# psu.net
KiCad netlist of a schematic drawn in EAGLE
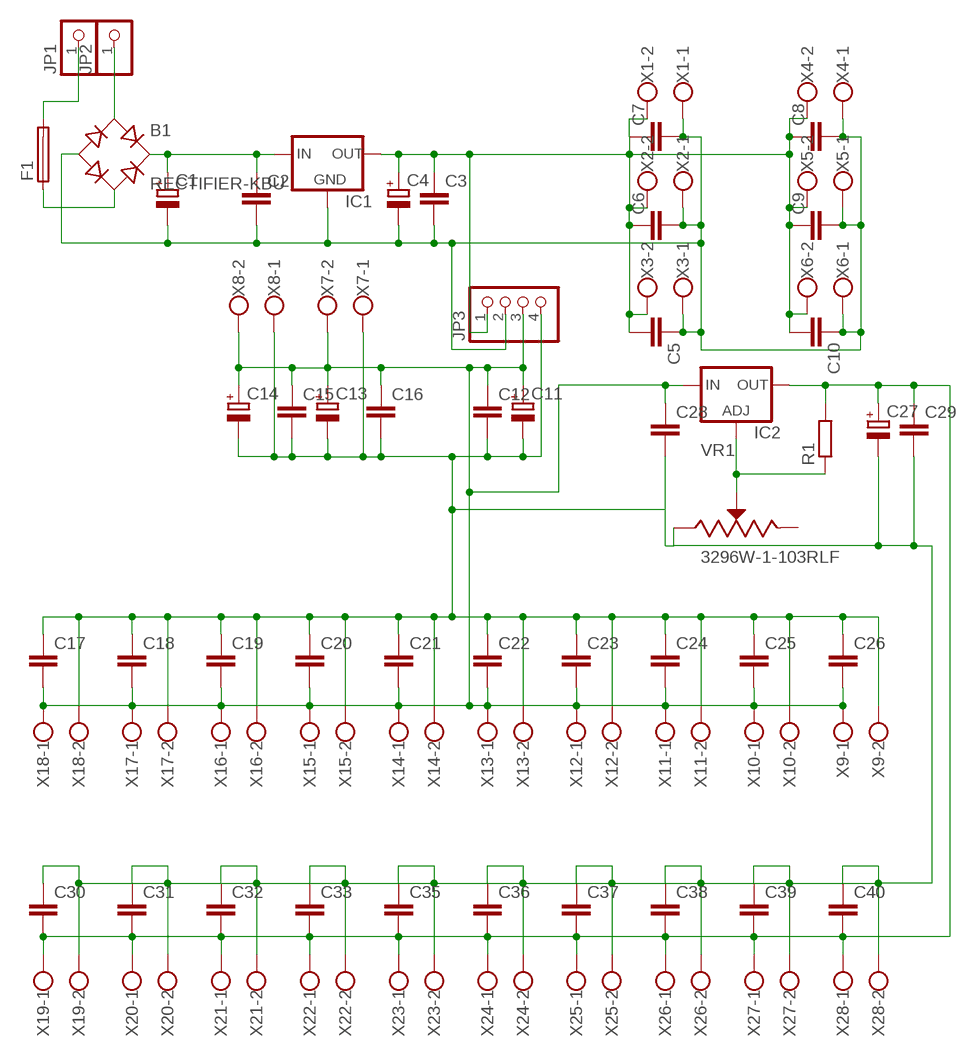
[diagram p0: schematic, sheet 1]

(export (version "E")
  (design (tool "Eeschema 10.0.6"))
  (components
    (comp (ref "B1")
      (value "RECTIFIER-KBU")
      (footprint "eagle-import:KBU")
      (libsource (lib "eagle-import") (part "RECTIFIER-KBU"))
    )
    (comp (ref "C1")
      (value "CPOL-EUE7.5-18")
      (footprint "eagle-import:E7,5-18")
      (libsource (lib "eagle-import") (part "CPOL-EUE7.5-18"))
    )
    (comp (ref "C2")
      (value "C-EU025-025X050")
      (footprint "eagle-import:C025-025X050")
      (libsource (lib "eagle-import") (part "C-EU025-025X050"))
    )
    (comp (ref "C3")
      (value "C-EU025-025X050")
      (footprint "eagle-import:C025-025X050")
      (libsource (lib "eagle-import") (part "C-EU025-025X050"))
    )
    (comp (ref "C4")
      (value "CPOL-EUE5-10.5")
      (footprint "eagle-import:E5-10,5")
      (libsource (lib "eagle-import") (part "CPOL-EUE5-10.5"))
    )
    (comp (ref "C5")
      (value "C-EU025-025X050")
      (footprint "eagle-import:C025-025X050")
      (libsource (lib "eagle-import") (part "C-EU025-025X050"))
    )
    (comp (ref "C6")
      (value "C-EU025-025X050")
      (footprint "eagle-import:C025-025X050")
      (libsource (lib "eagle-import") (part "C-EU025-025X050"))
    )
    (comp (ref "C7")
      (value "C-EU025-025X050")
      (footprint "eagle-import:C025-025X050")
      (libsource (lib "eagle-import") (part "C-EU025-025X050"))
    )
    (comp (ref "C8")
      (value "C-EU025-025X050")
      (footprint "eagle-import:C025-025X050")
      (libsource (lib "eagle-import") (part "C-EU025-025X050"))
    )
    (comp (ref "C9")
      (value "C-EU025-025X050")
      (footprint "eagle-import:C025-025X050")
      (libsource (lib "eagle-import") (part "C-EU025-025X050"))
    )
    (comp (ref "C10")
      (value "C-EU025-025X050")
      (footprint "eagle-import:C025-025X050")
      (libsource (lib "eagle-import") (part "C-EU025-025X050"))
    )
    (comp (ref "C11")
      (value "CPOL-EUE5-10.5")
      (footprint "eagle-import:E5-10,5")
      (libsource (lib "eagle-import") (part "CPOL-EUE5-10.5"))
    )
    (comp (ref "C12")
      (value "C-EU025-025X050")
      (footprint "eagle-import:C025-025X050")
      (libsource (lib "eagle-import") (part "C-EU025-025X050"))
    )
    (comp (ref "C13")
      (value "CPOL-EUE2.5-6")
      (footprint "eagle-import:E2,5-6")
      (libsource (lib "eagle-import") (part "CPOL-EUE2.5-6"))
    )
    (comp (ref "C14")
      (value "CPOL-EUE2.5-6")
      (footprint "eagle-import:E2,5-6")
      (libsource (lib "eagle-import") (part "CPOL-EUE2.5-6"))
    )
    (comp (ref "C15")
      (value "C-EU025-025X050")
      (footprint "eagle-import:C025-025X050")
      (libsource (lib "eagle-import") (part "C-EU025-025X050"))
    )
    (comp (ref "C16")
      (value "C-EU025-025X050")
      (footprint "eagle-import:C025-025X050")
      (libsource (lib "eagle-import") (part "C-EU025-025X050"))
    )
    (comp (ref "C17")
      (value "C-EU025-025X050")
      (footprint "eagle-import:C025-025X050")
      (libsource (lib "eagle-import") (part "C-EU025-025X050"))
    )
    (comp (ref "C18")
      (value "C-EU025-025X050")
      (footprint "eagle-import:C025-025X050")
      (libsource (lib "eagle-import") (part "C-EU025-025X050"))
    )
    (comp (ref "C19")
      (value "C-EU025-025X050")
      (footprint "eagle-import:C025-025X050")
      (libsource (lib "eagle-import") (part "C-EU025-025X050"))
    )
    (comp (ref "C20")
      (value "C-EU025-025X050")
      (footprint "eagle-import:C025-025X050")
      (libsource (lib "eagle-import") (part "C-EU025-025X050"))
    )
    (comp (ref "C21")
      (value "C-EU025-025X050")
      (footprint "eagle-import:C025-025X050")
      (libsource (lib "eagle-import") (part "C-EU025-025X050"))
    )
    (comp (ref "C22")
      (value "C-EU025-025X050")
      (footprint "eagle-import:C025-025X050")
      (libsource (lib "eagle-import") (part "C-EU025-025X050"))
    )
    (comp (ref "C23")
      (value "C-EU025-025X050")
      (footprint "eagle-import:C025-025X050")
      (libsource (lib "eagle-import") (part "C-EU025-025X050"))
    )
    (comp (ref "C24")
      (value "C-EU025-025X050")
      (footprint "eagle-import:C025-025X050")
      (libsource (lib "eagle-import") (part "C-EU025-025X050"))
    )
    (comp (ref "C25")
      (value "C-EU025-025X050")
      (footprint "eagle-import:C025-025X050")
      (libsource (lib "eagle-import") (part "C-EU025-025X050"))
    )
    (comp (ref "C26")
      (value "C-EU025-025X050")
      (footprint "eagle-import:C025-025X050")
      (libsource (lib "eagle-import") (part "C-EU025-025X050"))
    )
    (comp (ref "C27")
      (value "CPOL-EUE2.5-6")
      (footprint "eagle-import:E2,5-6")
      (libsource (lib "eagle-import") (part "CPOL-EUE2.5-6"))
    )
    (comp (ref "C28")
      (value "C-EU025-025X050")
      (footprint "eagle-import:C025-025X050")
      (libsource (lib "eagle-import") (part "C-EU025-025X050"))
    )
    (comp (ref "C29")
      (value "C-EU025-025X050")
      (footprint "eagle-import:C025-025X050")
      (libsource (lib "eagle-import") (part "C-EU025-025X050"))
    )
    (comp (ref "C30")
      (value "C-EU025-025X050")
      (footprint "eagle-import:C025-025X050")
      (libsource (lib "eagle-import") (part "C-EU025-025X050"))
    )
    (comp (ref "C31")
      (value "C-EU025-025X050")
      (footprint "eagle-import:C025-025X050")
      (libsource (lib "eagle-import") (part "C-EU025-025X050"))
    )
    (comp (ref "C32")
      (value "C-EU025-025X050")
      (footprint "eagle-import:C025-025X050")
      (libsource (lib "eagle-import") (part "C-EU025-025X050"))
    )
    (comp (ref "C33")
      (value "C-EU025-025X050")
      (footprint "eagle-import:C025-025X050")
      (libsource (lib "eagle-import") (part "C-EU025-025X050"))
    )
    (comp (ref "C35")
      (value "C-EU025-025X050")
      (footprint "eagle-import:C025-025X050")
      (libsource (lib "eagle-import") (part "C-EU025-025X050"))
    )
    (comp (ref "C36")
      (value "C-EU025-025X050")
      (footprint "eagle-import:C025-025X050")
      (libsource (lib "eagle-import") (part "C-EU025-025X050"))
    )
    (comp (ref "C37")
      (value "C-EU025-025X050")
      (footprint "eagle-import:C025-025X050")
      (libsource (lib "eagle-import") (part "C-EU025-025X050"))
    )
    (comp (ref "C38")
      (value "C-EU025-025X050")
      (footprint "eagle-import:C025-025X050")
      (libsource (lib "eagle-import") (part "C-EU025-025X050"))
    )
    (comp (ref "C39")
      (value "C-EU025-025X050")
      (footprint "eagle-import:C025-025X050")
      (libsource (lib "eagle-import") (part "C-EU025-025X050"))
    )
    (comp (ref "C40")
      (value "C-EU025-025X050")
      (footprint "eagle-import:C025-025X050")
      (libsource (lib "eagle-import") (part "C-EU025-025X050"))
    )
    (comp (ref "F1")
      (value "SH22,5")
      (footprint "eagle-import:SH22,5")
      (fields (field (name "MF") "SCHURTER") (field (name "MPN") "0031.8201"))
      (libsource (lib "eagle-import") (part "SH22,5"))
    )
    (comp (ref "IC1")
      (value "78XXS")
      (footprint "eagle-import:78XXS")
      (libsource (lib "eagle-import") (part "78XXS"))
    )
    (comp (ref "IC2")
      (value "LM317TS")
      (footprint "eagle-import:317TS")
      (libsource (lib "eagle-import") (part "LM317TS"))
    )
    (comp (ref "JP1")
      (value "PINHD-1X1")
      (footprint "eagle-import:1X01")
      (libsource (lib "eagle-import") (part "PINHD-1X1"))
    )
    (comp (ref "JP2")
      (value "PINHD-1X1")
      (footprint "eagle-import:1X01")
      (libsource (lib "eagle-import") (part "PINHD-1X1"))
    )
    (comp (ref "JP3")
      (value "PINHD-1X4")
      (footprint "eagle-import:1X04")
      (libsource (lib "eagle-import") (part "PINHD-1X4"))
    )
    (comp (ref "R1")
      (value "R-EU_0204/7")
      (footprint "eagle-import:0204_7")
      (libsource (lib "eagle-import") (part "R-EU_0204/7"))
    )
    (comp (ref "VR1")
      (value "3296W-1-103RLF")
      (footprint "eagle-import:TRIM_3296W-1-103RLF")
      (fields (field (name "MF") "Bourns"))
      (libsource (lib "eagle-import") (part "3296W-1-103RLF"))
    )
    (comp (ref "X1")
      (value "W237-102")
      (footprint "eagle-import:W237-102")
      (fields (field (name "MPN") "237-102"))
      (libsource (lib "eagle-import") (part "W237-102"))
    )
    (comp (ref "X2")
      (value "W237-102")
      (footprint "eagle-import:W237-102")
      (fields (field (name "MPN") "237-102"))
      (libsource (lib "eagle-import") (part "W237-102"))
    )
    (comp (ref "X3")
      (value "W237-102")
      (footprint "eagle-import:W237-102")
      (fields (field (name "MPN") "237-102"))
      (libsource (lib "eagle-import") (part "W237-102"))
    )
    (comp (ref "X4")
      (value "W237-102")
      (footprint "eagle-import:W237-102")
      (fields (field (name "MPN") "237-102"))
      (libsource (lib "eagle-import") (part "W237-102"))
    )
    (comp (ref "X5")
      (value "W237-102")
      (footprint "eagle-import:W237-102")
      (fields (field (name "MPN") "237-102"))
      (libsource (lib "eagle-import") (part "W237-102"))
    )
    (comp (ref "X6")
      (value "W237-102")
      (footprint "eagle-import:W237-102")
      (fields (field (name "MPN") "237-102"))
      (libsource (lib "eagle-import") (part "W237-102"))
    )
    (comp (ref "X7")
      (value "W237-102")
      (footprint "eagle-import:W237-102")
      (fields (field (name "MPN") "237-102"))
      (libsource (lib "eagle-import") (part "W237-102"))
    )
    (comp (ref "X8")
      (value "W237-102")
      (footprint "eagle-import:W237-102")
      (fields (field (name "MPN") "237-102"))
      (libsource (lib "eagle-import") (part "W237-102"))
    )
    (comp (ref "X9")
      (value "W237-102")
      (footprint "eagle-import:W237-102")
      (fields (field (name "MPN") "237-102"))
      (libsource (lib "eagle-import") (part "W237-102"))
    )
    (comp (ref "X10")
      (value "W237-102")
      (footprint "eagle-import:W237-102")
      (fields (field (name "MPN") "237-102"))
      (libsource (lib "eagle-import") (part "W237-102"))
    )
    (comp (ref "X11")
      (value "W237-102")
      (footprint "eagle-import:W237-102")
      (fields (field (name "MPN") "237-102"))
      (libsource (lib "eagle-import") (part "W237-102"))
    )
    (comp (ref "X12")
      (value "W237-102")
      (footprint "eagle-import:W237-102")
      (fields (field (name "MPN") "237-102"))
      (libsource (lib "eagle-import") (part "W237-102"))
    )
    (comp (ref "X13")
      (value "W237-102")
      (footprint "eagle-import:W237-102")
      (fields (field (name "MPN") "237-102"))
      (libsource (lib "eagle-import") (part "W237-102"))
    )
    (comp (ref "X14")
      (value "W237-102")
      (footprint "eagle-import:W237-102")
      (fields (field (name "MPN") "237-102"))
      (libsource (lib "eagle-import") (part "W237-102"))
    )
    (comp (ref "X15")
      (value "W237-102")
      (footprint "eagle-import:W237-102")
      (fields (field (name "MPN") "237-102"))
      (libsource (lib "eagle-import") (part "W237-102"))
    )
    (comp (ref "X16")
      (value "W237-102")
      (footprint "eagle-import:W237-102")
      (fields (field (name "MPN") "237-102"))
      (libsource (lib "eagle-import") (part "W237-102"))
    )
    (comp (ref "X17")
      (value "W237-102")
      (footprint "eagle-import:W237-102")
      (fields (field (name "MPN") "237-102"))
      (libsource (lib "eagle-import") (part "W237-102"))
    )
    (comp (ref "X18")
      (value "W237-102")
      (footprint "eagle-import:W237-102")
      (fields (field (name "MPN") "237-102"))
      (libsource (lib "eagle-import") (part "W237-102"))
    )
    (comp (ref "X19")
      (value "W237-102")
      (footprint "eagle-import:W237-102")
      (fields (field (name "MPN") "237-102"))
      (libsource (lib "eagle-import") (part "W237-102"))
    )
    (comp (ref "X20")
      (value "W237-102")
      (footprint "eagle-import:W237-102")
      (fields (field (name "MPN") "237-102"))
      (libsource (lib "eagle-import") (part "W237-102"))
    )
    (comp (ref "X21")
      (value "W237-102")
      (footprint "eagle-import:W237-102")
      (fields (field (name "MPN") "237-102"))
      (libsource (lib "eagle-import") (part "W237-102"))
    )
    (comp (ref "X22")
      (value "W237-102")
      (footprint "eagle-import:W237-102")
      (fields (field (name "MPN") "237-102"))
      (libsource (lib "eagle-import") (part "W237-102"))
    )
    (comp (ref "X23")
      (value "W237-102")
      (footprint "eagle-import:W237-102")
      (fields (field (name "MPN") "237-102"))
      (libsource (lib "eagle-import") (part "W237-102"))
    )
    (comp (ref "X24")
      (value "W237-102")
      (footprint "eagle-import:W237-102")
      (fields (field (name "MPN") "237-102"))
      (libsource (lib "eagle-import") (part "W237-102"))
    )
    (comp (ref "X25")
      (value "W237-102")
      (footprint "eagle-import:W237-102")
      (fields (field (name "MPN") "237-102"))
      (libsource (lib "eagle-import") (part "W237-102"))
    )
    (comp (ref "X26")
      (value "W237-102")
      (footprint "eagle-import:W237-102")
      (fields (field (name "MPN") "237-102"))
      (libsource (lib "eagle-import") (part "W237-102"))
    )
    (comp (ref "X27")
      (value "W237-102")
      (footprint "eagle-import:W237-102")
      (fields (field (name "MPN") "237-102"))
      (libsource (lib "eagle-import") (part "W237-102"))
    )
    (comp (ref "X28")
      (value "W237-102")
      (footprint "eagle-import:W237-102")
      (fields (field (name "MPN") "237-102"))
      (libsource (lib "eagle-import") (part "W237-102"))
    )
  )
  (nets
    (net (code "1") (name "Net-(B1-Pad+)") (class "Default")
      (node (ref "B1") (pin "+") (pinfunction "+_+") (pintype "passive"))
      (node (ref "C1") (pin "+") (pinfunction "+_+") (pintype "passive"))
      (node (ref "C2") (pin "1") (pinfunction "1_1") (pintype "passive"))
      (node (ref "IC1") (pin "IN") (pinfunction "IN_IN") (pintype "input"))
    )
    (net (code "2") (name "Net-(B1-PadAC1)") (class "Default")
      (node (ref "B1") (pin "AC1") (pinfunction "AC1_AC1") (pintype "passive"))
      (node (ref "JP2") (pin "1") (pinfunction "1_1") (pintype "passive"))
    )
    (net (code "3") (name "Net-(B1-PadAC2)") (class "Default")
      (node (ref "B1") (pin "AC2") (pinfunction "AC2_AC2") (pintype "passive"))
      (node (ref "F1") (pin "1") (pinfunction "1_1") (pintype "passive"))
    )
    (net (code "4") (name "Net-(F1-Pad2)") (class "Default")
      (node (ref "F1") (pin "2") (pinfunction "2_2") (pintype "passive"))
      (node (ref "JP1") (pin "1") (pinfunction "1_1") (pintype "passive"))
    )
    (net (code "5") (name "Net-(IC2-ADJ)") (class "Default")
      (node (ref "IC2") (pin "1") (pinfunction "ADJ_1") (pintype "input"))
      (node (ref "R1") (pin "1") (pinfunction "1_1") (pintype "passive"))
      (node (ref "VR1") (pin "2") (pinfunction "WIPER_2") (pintype "passive"))
    )
    (net (code "6") (name "Net-(IC2-IN)") (class "Default")
      (node (ref "C11") (pin "+") (pinfunction "+_+") (pintype "passive"))
      (node (ref "C12") (pin "1") (pinfunction "1_1") (pintype "passive"))
      (node (ref "C13") (pin "+") (pinfunction "+_+") (pintype "passive"))
      (node (ref "C14") (pin "+") (pinfunction "+_+") (pintype "passive"))
      (node (ref "C15") (pin "1") (pinfunction "1_1") (pintype "passive"))
      (node (ref "C16") (pin "1") (pinfunction "1_1") (pintype "passive"))
      (node (ref "C17") (pin "2") (pinfunction "2_2") (pintype "passive"))
      (node (ref "C18") (pin "2") (pinfunction "2_2") (pintype "passive"))
      (node (ref "C19") (pin "2") (pinfunction "2_2") (pintype "passive"))
      (node (ref "C20") (pin "2") (pinfunction "2_2") (pintype "passive"))
      (node (ref "C21") (pin "2") (pinfunction "2_2") (pintype "passive"))
      (node (ref "C22") (pin "2") (pinfunction "2_2") (pintype "passive"))
      (node (ref "C23") (pin "2") (pinfunction "2_2") (pintype "passive"))
      (node (ref "C24") (pin "2") (pinfunction "2_2") (pintype "passive"))
      (node (ref "C25") (pin "2") (pinfunction "2_2") (pintype "passive"))
      (node (ref "C26") (pin "2") (pinfunction "2_2") (pintype "passive"))
      (node (ref "C28") (pin "1") (pinfunction "1_1") (pintype "passive"))
      (node (ref "IC2") (pin "3") (pinfunction "IN_3") (pintype "input"))
      (node (ref "JP3") (pin "3") (pinfunction "3_3") (pintype "passive"))
      (node (ref "X10") (pin "1") (pinfunction "KL_1") (pintype "passive"))
      (node (ref "X11") (pin "1") (pinfunction "KL_1") (pintype "passive"))
      (node (ref "X12") (pin "1") (pinfunction "KL_1") (pintype "passive"))
      (node (ref "X13") (pin "1") (pinfunction "KL_1") (pintype "passive"))
      (node (ref "X14") (pin "1") (pinfunction "KL_1") (pintype "passive"))
      (node (ref "X15") (pin "1") (pinfunction "KL_1") (pintype "passive"))
      (node (ref "X16") (pin "1") (pinfunction "KL_1") (pintype "passive"))
      (node (ref "X17") (pin "1") (pinfunction "KL_1") (pintype "passive"))
      (node (ref "X18") (pin "1") (pinfunction "KL_1") (pintype "passive"))
      (node (ref "X7") (pin "2") (pinfunction "KL_2") (pintype "passive"))
      (node (ref "X8") (pin "2") (pinfunction "KL_2") (pintype "passive"))
      (node (ref "X9") (pin "1") (pinfunction "KL_1") (pintype "passive"))
    )
    (net (code "7") (name "Net-(IC2-OUT)") (class "Default")
      (node (ref "C27") (pin "+") (pinfunction "+_+") (pintype "passive"))
      (node (ref "C29") (pin "1") (pinfunction "1_1") (pintype "passive"))
      (node (ref "C30") (pin "2") (pinfunction "2_2") (pintype "passive"))
      (node (ref "C31") (pin "2") (pinfunction "2_2") (pintype "passive"))
      (node (ref "C32") (pin "2") (pinfunction "2_2") (pintype "passive"))
      (node (ref "C33") (pin "2") (pinfunction "2_2") (pintype "passive"))
      (node (ref "C35") (pin "2") (pinfunction "2_2") (pintype "passive"))
      (node (ref "C36") (pin "2") (pinfunction "2_2") (pintype "passive"))
      (node (ref "C37") (pin "2") (pinfunction "2_2") (pintype "passive"))
      (node (ref "C38") (pin "2") (pinfunction "2_2") (pintype "passive"))
      (node (ref "C39") (pin "2") (pinfunction "2_2") (pintype "passive"))
      (node (ref "C40") (pin "2") (pinfunction "2_2") (pintype "passive"))
      (node (ref "IC2") (pin "2") (pinfunction "OUT_2") (pintype "passive"))
      (node (ref "R1") (pin "2") (pinfunction "2_2") (pintype "passive"))
      (node (ref "X19") (pin "1") (pinfunction "KL_1") (pintype "passive"))
      (node (ref "X20") (pin "1") (pinfunction "KL_1") (pintype "passive"))
      (node (ref "X21") (pin "1") (pinfunction "KL_1") (pintype "passive"))
      (node (ref "X22") (pin "1") (pinfunction "KL_1") (pintype "passive"))
      (node (ref "X23") (pin "1") (pinfunction "KL_1") (pintype "passive"))
      (node (ref "X24") (pin "1") (pinfunction "KL_1") (pintype "passive"))
      (node (ref "X25") (pin "1") (pinfunction "KL_1") (pintype "passive"))
      (node (ref "X26") (pin "1") (pinfunction "KL_1") (pintype "passive"))
      (node (ref "X27") (pin "1") (pinfunction "KL_1") (pintype "passive"))
      (node (ref "X28") (pin "1") (pinfunction "KL_1") (pintype "passive"))
    )
    (net (code "8") (name "Net-(VR1-CCW)") (class "Default")
      (node (ref "C11") (pin "-") (pinfunction "-_-") (pintype "passive"))
      (node (ref "C12") (pin "2") (pinfunction "2_2") (pintype "passive"))
      (node (ref "C13") (pin "-") (pinfunction "-_-") (pintype "passive"))
      (node (ref "C14") (pin "-") (pinfunction "-_-") (pintype "passive"))
      (node (ref "C15") (pin "2") (pinfunction "2_2") (pintype "passive"))
      (node (ref "C16") (pin "2") (pinfunction "2_2") (pintype "passive"))
      (node (ref "C17") (pin "1") (pinfunction "1_1") (pintype "passive"))
      (node (ref "C18") (pin "1") (pinfunction "1_1") (pintype "passive"))
      (node (ref "C19") (pin "1") (pinfunction "1_1") (pintype "passive"))
      (node (ref "C20") (pin "1") (pinfunction "1_1") (pintype "passive"))
      (node (ref "C21") (pin "1") (pinfunction "1_1") (pintype "passive"))
      (node (ref "C22") (pin "1") (pinfunction "1_1") (pintype "passive"))
      (node (ref "C23") (pin "1") (pinfunction "1_1") (pintype "passive"))
      (node (ref "C24") (pin "1") (pinfunction "1_1") (pintype "passive"))
      (node (ref "C25") (pin "1") (pinfunction "1_1") (pintype "passive"))
      (node (ref "C26") (pin "1") (pinfunction "1_1") (pintype "passive"))
      (node (ref "C27") (pin "-") (pinfunction "-_-") (pintype "passive"))
      (node (ref "C28") (pin "2") (pinfunction "2_2") (pintype "passive"))
      (node (ref "C29") (pin "2") (pinfunction "2_2") (pintype "passive"))
      (node (ref "C30") (pin "1") (pinfunction "1_1") (pintype "passive"))
      (node (ref "C31") (pin "1") (pinfunction "1_1") (pintype "passive"))
      (node (ref "C32") (pin "1") (pinfunction "1_1") (pintype "passive"))
      (node (ref "C33") (pin "1") (pinfunction "1_1") (pintype "passive"))
      (node (ref "C35") (pin "1") (pinfunction "1_1") (pintype "passive"))
      (node (ref "C36") (pin "1") (pinfunction "1_1") (pintype "passive"))
      (node (ref "C37") (pin "1") (pinfunction "1_1") (pintype "passive"))
      (node (ref "C38") (pin "1") (pinfunction "1_1") (pintype "passive"))
      (node (ref "C39") (pin "1") (pinfunction "1_1") (pintype "passive"))
      (node (ref "C40") (pin "1") (pinfunction "1_1") (pintype "passive"))
      (node (ref "JP3") (pin "4") (pinfunction "4_4") (pintype "passive"))
      (node (ref "VR1") (pin "1") (pinfunction "CCW_1") (pintype "passive"))
      (node (ref "X10") (pin "2") (pinfunction "KL_2") (pintype "passive"))
      (node (ref "X11") (pin "2") (pinfunction "KL_2") (pintype "passive"))
      (node (ref "X12") (pin "2") (pinfunction "KL_2") (pintype "passive"))
      (node (ref "X13") (pin "2") (pinfunction "KL_2") (pintype "passive"))
      (node (ref "X14") (pin "2") (pinfunction "KL_2") (pintype "passive"))
      (node (ref "X15") (pin "2") (pinfunction "KL_2") (pintype "passive"))
      (node (ref "X16") (pin "2") (pinfunction "KL_2") (pintype "passive"))
      (node (ref "X17") (pin "2") (pinfunction "KL_2") (pintype "passive"))
      (node (ref "X18") (pin "2") (pinfunction "KL_2") (pintype "passive"))
      (node (ref "X19") (pin "2") (pinfunction "KL_2") (pintype "passive"))
      (node (ref "X20") (pin "2") (pinfunction "KL_2") (pintype "passive"))
      (node (ref "X21") (pin "2") (pinfunction "KL_2") (pintype "passive"))
      (node (ref "X22") (pin "2") (pinfunction "KL_2") (pintype "passive"))
      (node (ref "X23") (pin "2") (pinfunction "KL_2") (pintype "passive"))
      (node (ref "X24") (pin "2") (pinfunction "KL_2") (pintype "passive"))
      (node (ref "X25") (pin "2") (pinfunction "KL_2") (pintype "passive"))
      (node (ref "X26") (pin "2") (pinfunction "KL_2") (pintype "passive"))
      (node (ref "X27") (pin "2") (pinfunction "KL_2") (pintype "passive"))
      (node (ref "X28") (pin "2") (pinfunction "KL_2") (pintype "passive"))
      (node (ref "X7") (pin "1") (pinfunction "KL_1") (pintype "passive"))
      (node (ref "X8") (pin "1") (pinfunction "KL_1") (pintype "passive"))
      (node (ref "X9") (pin "2") (pinfunction "KL_2") (pintype "passive"))
    )
    (net (code "9") (name "Net-(X1A-KL)") (class "Default")
      (node (ref "B1") (pin "-") (pinfunction "-_-") (pintype "passive"))
      (node (ref "C1") (pin "-") (pinfunction "-_-") (pintype "passive"))
      (node (ref "C10") (pin "1") (pinfunction "1_1") (pintype "passive"))
      (node (ref "C2") (pin "2") (pinfunction "2_2") (pintype "passive"))
      (node (ref "C3") (pin "2") (pinfunction "2_2") (pintype "passive"))
      (node (ref "C4") (pin "-") (pinfunction "-_-") (pintype "passive"))
      (node (ref "C5") (pin "1") (pinfunction "1_1") (pintype "passive"))
      (node (ref "C6") (pin "2") (pinfunction "2_2") (pintype "passive"))
      (node (ref "C7") (pin "2") (pinfunction "2_2") (pintype "passive"))
      (node (ref "C8") (pin "2") (pinfunction "2_2") (pintype "passive"))
      (node (ref "C9") (pin "2") (pinfunction "2_2") (pintype "passive"))
      (node (ref "IC1") (pin "GND") (pinfunction "GND_GND") (pintype "input"))
      (node (ref "JP3") (pin "2") (pinfunction "2_2") (pintype "passive"))
      (node (ref "X1") (pin "1") (pinfunction "KL_1") (pintype "passive"))
      (node (ref "X2") (pin "1") (pinfunction "KL_1") (pintype "passive"))
      (node (ref "X3") (pin "1") (pinfunction "KL_1") (pintype "passive"))
      (node (ref "X4") (pin "1") (pinfunction "KL_1") (pintype "passive"))
      (node (ref "X5") (pin "1") (pinfunction "KL_1") (pintype "passive"))
      (node (ref "X6") (pin "1") (pinfunction "KL_1") (pintype "passive"))
    )
    (net (code "10") (name "Net-(X1B-KL)") (class "Default")
      (node (ref "C10") (pin "2") (pinfunction "2_2") (pintype "passive"))
      (node (ref "C3") (pin "1") (pinfunction "1_1") (pintype "passive"))
      (node (ref "C4") (pin "+") (pinfunction "+_+") (pintype "passive"))
      (node (ref "C5") (pin "2") (pinfunction "2_2") (pintype "passive"))
      (node (ref "C6") (pin "1") (pinfunction "1_1") (pintype "passive"))
      (node (ref "C7") (pin "1") (pinfunction "1_1") (pintype "passive"))
      (node (ref "C8") (pin "1") (pinfunction "1_1") (pintype "passive"))
      (node (ref "C9") (pin "1") (pinfunction "1_1") (pintype "passive"))
      (node (ref "IC1") (pin "OUT") (pinfunction "OUT_OUT") (pintype "passive"))
      (node (ref "JP3") (pin "1") (pinfunction "1_1") (pintype "passive"))
      (node (ref "X1") (pin "2") (pinfunction "KL_2") (pintype "passive"))
      (node (ref "X2") (pin "2") (pinfunction "KL_2") (pintype "passive"))
      (node (ref "X3") (pin "2") (pinfunction "KL_2") (pintype "passive"))
      (node (ref "X4") (pin "2") (pinfunction "KL_2") (pintype "passive"))
      (node (ref "X5") (pin "2") (pinfunction "KL_2") (pintype "passive"))
      (node (ref "X6") (pin "2") (pinfunction "KL_2") (pintype "passive"))
    )
    (net (code "11") (name "unconnected-(VR1-CW-Pad3)") (class "Default")
      (node (ref "VR1") (pin "3") (pinfunction "CW_3") (pintype "passive"))
    )
  )
)
